# Motor.net
KiCad netlist of a schematic drawn in Altium Designer
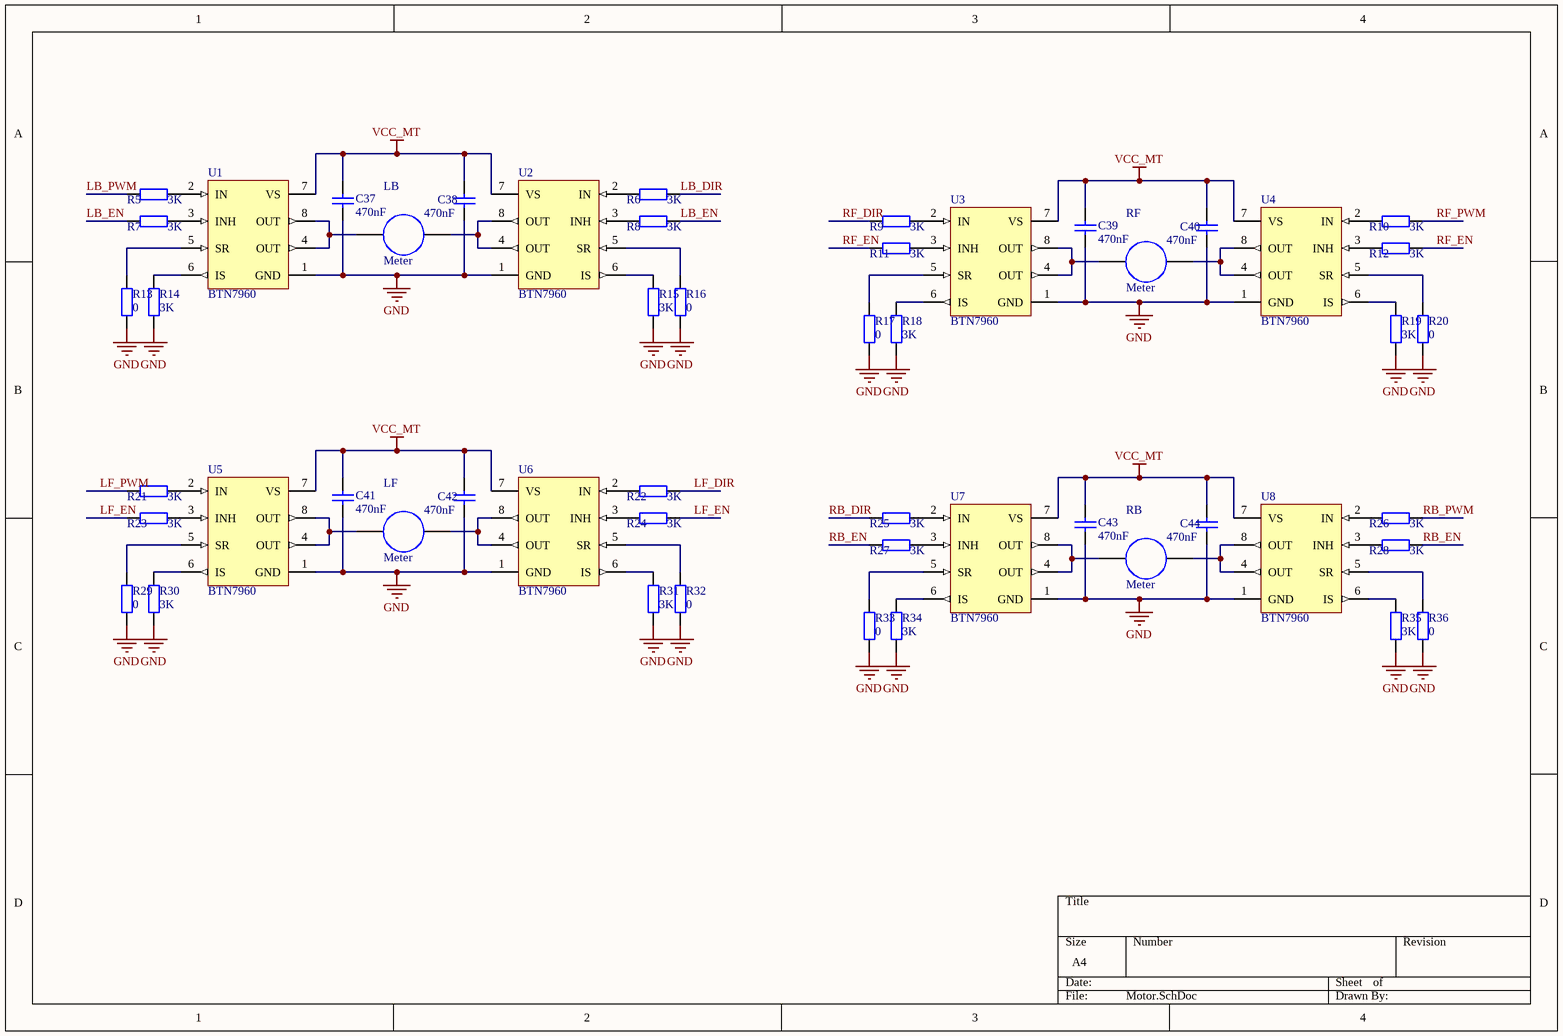
[diagram p0: Motor.SchDoc]

(export (version "E")
  (design (tool "Eeschema 10.0.6"))
  (components
    (comp (ref "C37")
      (value "470nF")
      (footprint "0805_C")
      (description "Capacitor")
      (fields (field (name "Comment") "Cap") (field (name "PUBLISHER") "Altium Limited"))
      (libsource (lib "Miscellaneous Devices") (part "Cap"))
    )
    (comp (ref "C38")
      (value "470nF")
      (footprint "MKV58:0805_C")
      (description "Capacitor")
      (fields (field (name "Comment") "Cap") (field (name "PUBLISHER") "Altium Limited"))
      (libsource (lib "Miscellaneous Devices") (part "Cap"))
    )
    (comp (ref "C39")
      (value "470nF")
      (footprint "0805_C")
      (description "Capacitor")
      (fields (field (name "Comment") "Cap") (field (name "PUBLISHER") "Altium Limited"))
      (libsource (lib "Miscellaneous Devices") (part "Cap"))
    )
    (comp (ref "C40")
      (value "470nF")
      (footprint "MKV58:0805_C")
      (description "Capacitor")
      (fields (field (name "Comment") "Cap") (field (name "PUBLISHER") "Altium Limited"))
      (libsource (lib "Miscellaneous Devices") (part "Cap"))
    )
    (comp (ref "C41")
      (value "470nF")
      (footprint "0805_C")
      (description "Capacitor")
      (fields (field (name "Comment") "Cap") (field (name "PUBLISHER") "Altium Limited"))
      (libsource (lib "Miscellaneous Devices") (part "Cap"))
    )
    (comp (ref "C42")
      (value "470nF")
      (footprint "MKV58:0805_C")
      (description "Capacitor")
      (fields (field (name "Comment") "Cap") (field (name "PUBLISHER") "Altium Limited"))
      (libsource (lib "Miscellaneous Devices") (part "Cap"))
    )
    (comp (ref "C43")
      (value "470nF")
      (footprint "0805_C")
      (description "Capacitor")
      (fields (field (name "Comment") "Cap") (field (name "PUBLISHER") "Altium Limited"))
      (libsource (lib "Miscellaneous Devices") (part "Cap"))
    )
    (comp (ref "C44")
      (value "470nF")
      (footprint "MKV58:0805_C")
      (description "Capacitor")
      (fields (field (name "Comment") "Cap") (field (name "PUBLISHER") "Altium Limited"))
      (libsource (lib "Miscellaneous Devices") (part "Cap"))
    )
    (comp (ref "LB")
      (value "Meter")
      (footprint "Head_Small")
      (description "Indicating Instrument")
      (fields (field (name "PUBLISHER") "Altium Limited"))
      (libsource (lib "Miscellaneous Devices") (part "Meter"))
    )
    (comp (ref "LF")
      (value "Meter")
      (footprint "Head_Small")
      (description "Indicating Instrument")
      (fields (field (name "PUBLISHER") "Altium Limited"))
      (libsource (lib "Miscellaneous Devices") (part "Meter"))
    )
    (comp (ref "R5")
      (value "3K")
      (footprint "0805_R")
      (description "Resistor")
      (fields (field (name "Comment") "Res2") (field (name "PUBLISHER") "Altium Limited"))
      (libsource (lib "") (part "Res2_3"))
    )
    (comp (ref "R6")
      (value "3K")
      (footprint "0805_R")
      (description "Resistor")
      (fields (field (name "Comment") "Res2") (field (name "PUBLISHER") "Altium Limited"))
      (libsource (lib "") (part "Res2_3"))
    )
    (comp (ref "R7")
      (value "3K")
      (footprint "0805_R")
      (description "Resistor")
      (fields (field (name "Comment") "Res2") (field (name "PUBLISHER") "Altium Limited"))
      (libsource (lib "") (part "Res2_2"))
    )
    (comp (ref "R8")
      (value "3K")
      (footprint "0805_R")
      (description "Resistor")
      (fields (field (name "Comment") "Res2") (field (name "PUBLISHER") "Altium Limited"))
      (libsource (lib "Miscellaneous Devices") (part "Res2"))
    )
    (comp (ref "R9")
      (value "3K")
      (footprint "0805_R")
      (description "Resistor")
      (fields (field (name "Comment") "Res2") (field (name "PUBLISHER") "Altium Limited"))
      (libsource (lib "") (part "Res2_3"))
    )
    (comp (ref "R10")
      (value "3K")
      (footprint "0805_R")
      (description "Resistor")
      (fields (field (name "Comment") "Res2") (field (name "PUBLISHER") "Altium Limited"))
      (libsource (lib "") (part "Res2_3"))
    )
    (comp (ref "R11")
      (value "3K")
      (footprint "0805_R")
      (description "Resistor")
      (fields (field (name "Comment") "Res2") (field (name "PUBLISHER") "Altium Limited"))
      (libsource (lib "") (part "Res2_2"))
    )
    (comp (ref "R12")
      (value "3K")
      (footprint "0805_R")
      (description "Resistor")
      (fields (field (name "Comment") "Res2") (field (name "PUBLISHER") "Altium Limited"))
      (libsource (lib "Miscellaneous Devices") (part "Res2"))
    )
    (comp (ref "R13")
      (value "0")
      (footprint "0805_R")
      (description "Resistor")
      (fields (field (name "Comment") "Res2") (field (name "PUBLISHER") "Altium Limited"))
      (libsource (lib "") (part "Res2_1"))
    )
    (comp (ref "R14")
      (value "3K")
      (footprint "0805_R")
      (description "Resistor")
      (fields (field (name "Comment") "Res2") (field (name "PUBLISHER") "Altium Limited"))
      (libsource (lib "") (part "Res2_1"))
    )
    (comp (ref "R15")
      (value "3K")
      (footprint "0805_R")
      (description "Resistor")
      (fields (field (name "Comment") "Res2") (field (name "PUBLISHER") "Altium Limited"))
      (libsource (lib "") (part "Res2_2"))
    )
    (comp (ref "R16")
      (value "0")
      (footprint "0805_R")
      (description "Resistor")
      (fields (field (name "Comment") "Res2") (field (name "PUBLISHER") "Altium Limited"))
      (libsource (lib "") (part "Res2_2"))
    )
    (comp (ref "R17")
      (value "0")
      (footprint "0805_R")
      (description "Resistor")
      (fields (field (name "Comment") "Res2") (field (name "PUBLISHER") "Altium Limited"))
      (libsource (lib "") (part "Res2_1"))
    )
    (comp (ref "R18")
      (value "3K")
      (footprint "0805_R")
      (description "Resistor")
      (fields (field (name "Comment") "Res2") (field (name "PUBLISHER") "Altium Limited"))
      (libsource (lib "") (part "Res2_1"))
    )
    (comp (ref "R19")
      (value "3K")
      (footprint "0805_R")
      (description "Resistor")
      (fields (field (name "Comment") "Res2") (field (name "PUBLISHER") "Altium Limited"))
      (libsource (lib "") (part "Res2_2"))
    )
    (comp (ref "R20")
      (value "0")
      (footprint "0805_R")
      (description "Resistor")
      (fields (field (name "Comment") "Res2") (field (name "PUBLISHER") "Altium Limited"))
      (libsource (lib "") (part "Res2_2"))
    )
    (comp (ref "R21")
      (value "3K")
      (footprint "0805_R")
      (description "Resistor")
      (fields (field (name "Comment") "Res2") (field (name "PUBLISHER") "Altium Limited"))
      (libsource (lib "") (part "Res2_3"))
    )
    (comp (ref "R22")
      (value "3K")
      (footprint "0805_R")
      (description "Resistor")
      (fields (field (name "Comment") "Res2") (field (name "PUBLISHER") "Altium Limited"))
      (libsource (lib "") (part "Res2_3"))
    )
    (comp (ref "R23")
      (value "3K")
      (footprint "0805_R")
      (description "Resistor")
      (fields (field (name "Comment") "Res2") (field (name "PUBLISHER") "Altium Limited"))
      (libsource (lib "") (part "Res2_2"))
    )
    (comp (ref "R24")
      (value "3K")
      (footprint "0805_R")
      (description "Resistor")
      (fields (field (name "Comment") "Res2") (field (name "PUBLISHER") "Altium Limited"))
      (libsource (lib "Miscellaneous Devices") (part "Res2"))
    )
    (comp (ref "R25")
      (value "3K")
      (footprint "0805_R")
      (description "Resistor")
      (fields (field (name "Comment") "Res2") (field (name "PUBLISHER") "Altium Limited"))
      (libsource (lib "") (part "Res2_3"))
    )
    (comp (ref "R26")
      (value "3K")
      (footprint "0805_R")
      (description "Resistor")
      (fields (field (name "Comment") "Res2") (field (name "PUBLISHER") "Altium Limited"))
      (libsource (lib "") (part "Res2_3"))
    )
    (comp (ref "R27")
      (value "3K")
      (footprint "0805_R")
      (description "Resistor")
      (fields (field (name "Comment") "Res2") (field (name "PUBLISHER") "Altium Limited"))
      (libsource (lib "") (part "Res2_2"))
    )
    (comp (ref "R28")
      (value "3K")
      (footprint "0805_R")
      (description "Resistor")
      (fields (field (name "Comment") "Res2") (field (name "PUBLISHER") "Altium Limited"))
      (libsource (lib "Miscellaneous Devices") (part "Res2"))
    )
    (comp (ref "R29")
      (value "0")
      (footprint "0805_R")
      (description "Resistor")
      (fields (field (name "Comment") "Res2") (field (name "PUBLISHER") "Altium Limited"))
      (libsource (lib "") (part "Res2_1"))
    )
    (comp (ref "R30")
      (value "3K")
      (footprint "0805_R")
      (description "Resistor")
      (fields (field (name "Comment") "Res2") (field (name "PUBLISHER") "Altium Limited"))
      (libsource (lib "") (part "Res2_1"))
    )
    (comp (ref "R31")
      (value "3K")
      (footprint "0805_R")
      (description "Resistor")
      (fields (field (name "Comment") "Res2") (field (name "PUBLISHER") "Altium Limited"))
      (libsource (lib "") (part "Res2_2"))
    )
    (comp (ref "R32")
      (value "0")
      (footprint "0805_R")
      (description "Resistor")
      (fields (field (name "Comment") "Res2") (field (name "PUBLISHER") "Altium Limited"))
      (libsource (lib "") (part "Res2_2"))
    )
    (comp (ref "R33")
      (value "0")
      (footprint "0805_R")
      (description "Resistor")
      (fields (field (name "Comment") "Res2") (field (name "PUBLISHER") "Altium Limited"))
      (libsource (lib "") (part "Res2_1"))
    )
    (comp (ref "R34")
      (value "3K")
      (footprint "0805_R")
      (description "Resistor")
      (fields (field (name "Comment") "Res2") (field (name "PUBLISHER") "Altium Limited"))
      (libsource (lib "") (part "Res2_1"))
    )
    (comp (ref "R35")
      (value "3K")
      (footprint "0805_R")
      (description "Resistor")
      (fields (field (name "Comment") "Res2") (field (name "PUBLISHER") "Altium Limited"))
      (libsource (lib "") (part "Res2_2"))
    )
    (comp (ref "R36")
      (value "0")
      (footprint "0805_R")
      (description "Resistor")
      (fields (field (name "Comment") "Res2") (field (name "PUBLISHER") "Altium Limited"))
      (libsource (lib "") (part "Res2_2"))
    )
    (comp (ref "RB")
      (value "Meter")
      (footprint "Head_Small")
      (description "Indicating Instrument")
      (fields (field (name "PUBLISHER") "Altium Limited"))
      (libsource (lib "Miscellaneous Devices") (part "Meter"))
    )
    (comp (ref "RF")
      (value "Meter")
      (footprint "Head_Small")
      (description "Indicating Instrument")
      (fields (field (name "PUBLISHER") "Altium Limited"))
      (libsource (lib "Miscellaneous Devices") (part "Meter"))
    )
    (comp (ref "U1") (value "BTN7960") (footprint "TO-263-7") (libsource (lib "") (part "BTN7960_1")))
    (comp (ref "U2") (value "BTN7960") (footprint "TO-263-7") (libsource (lib "BTN7960") (part "BTN7960")))
    (comp (ref "U3") (value "BTN7960") (footprint "TO-263-7") (libsource (lib "") (part "BTN7960_1")))
    (comp (ref "U4") (value "BTN7960") (footprint "TO-263-7") (libsource (lib "BTN7960") (part "BTN7960")))
    (comp (ref "U5") (value "BTN7960") (footprint "TO-263-7") (libsource (lib "") (part "BTN7960_1")))
    (comp (ref "U6") (value "BTN7960") (footprint "TO-263-7") (libsource (lib "BTN7960") (part "BTN7960")))
    (comp (ref "U7") (value "BTN7960") (footprint "TO-263-7") (libsource (lib "") (part "BTN7960_1")))
    (comp (ref "U8") (value "BTN7960") (footprint "TO-263-7") (libsource (lib "BTN7960") (part "BTN7960")))
  )
  (nets
    (net (code "1") (name "/LB_DIR") (class "Default")
      (node (ref "R6") (pin "1") (pinfunction "1_1") (pintype "passive"))
    )
    (net (code "2") (name "/LB_EN") (class "Default")
      (node (ref "R7") (pin "1") (pinfunction "1_1") (pintype "passive"))
      (node (ref "R8") (pin "1") (pinfunction "1_1") (pintype "passive"))
    )
    (net (code "3") (name "/LB_PWM") (class "Default")
      (node (ref "R5") (pin "2") (pinfunction "2_2") (pintype "passive"))
    )
    (net (code "4") (name "/LF_DIR") (class "Default")
      (node (ref "R22") (pin "1") (pinfunction "1_1") (pintype "passive"))
    )
    (net (code "5") (name "/LF_EN") (class "Default")
      (node (ref "R23") (pin "1") (pinfunction "1_1") (pintype "passive"))
      (node (ref "R24") (pin "1") (pinfunction "1_1") (pintype "passive"))
    )
    (net (code "6") (name "/LF_PWM") (class "Default")
      (node (ref "R21") (pin "2") (pinfunction "2_2") (pintype "passive"))
    )
    (net (code "7") (name "/RB_DIR") (class "Default")
      (node (ref "R25") (pin "2") (pinfunction "2_2") (pintype "passive"))
    )
    (net (code "8") (name "/RB_EN") (class "Default")
      (node (ref "R27") (pin "1") (pinfunction "1_1") (pintype "passive"))
      (node (ref "R28") (pin "1") (pinfunction "1_1") (pintype "passive"))
    )
    (net (code "9") (name "/RB_PWM") (class "Default")
      (node (ref "R26") (pin "1") (pinfunction "1_1") (pintype "passive"))
    )
    (net (code "10") (name "/RF_DIR") (class "Default")
      (node (ref "R9") (pin "2") (pinfunction "2_2") (pintype "passive"))
    )
    (net (code "11") (name "/RF_EN") (class "Default")
      (node (ref "R11") (pin "1") (pinfunction "1_1") (pintype "passive"))
      (node (ref "R12") (pin "1") (pinfunction "1_1") (pintype "passive"))
    )
    (net (code "12") (name "/RF_PWM") (class "Default")
      (node (ref "R10") (pin "1") (pinfunction "1_1") (pintype "passive"))
    )
    (net (code "13") (name "GND") (class "Default")
      (node (ref "C37") (pin "1") (pinfunction "1_1") (pintype "passive"))
      (node (ref "C38") (pin "2") (pinfunction "2_2") (pintype "passive"))
      (node (ref "C39") (pin "1") (pinfunction "1_1") (pintype "passive"))
      (node (ref "C40") (pin "2") (pinfunction "2_2") (pintype "passive"))
      (node (ref "C41") (pin "1") (pinfunction "1_1") (pintype "passive"))
      (node (ref "C42") (pin "2") (pinfunction "2_2") (pintype "passive"))
      (node (ref "C43") (pin "1") (pinfunction "1_1") (pintype "passive"))
      (node (ref "C44") (pin "2") (pinfunction "2_2") (pintype "passive"))
      (node (ref "R13") (pin "1") (pinfunction "1_1") (pintype "passive"))
      (node (ref "R14") (pin "1") (pinfunction "1_1") (pintype "passive"))
      (node (ref "R15") (pin "1") (pinfunction "1_1") (pintype "passive"))
      (node (ref "R16") (pin "1") (pinfunction "1_1") (pintype "passive"))
      (node (ref "R17") (pin "1") (pinfunction "1_1") (pintype "passive"))
      (node (ref "R18") (pin "1") (pinfunction "1_1") (pintype "passive"))
      (node (ref "R19") (pin "1") (pinfunction "1_1") (pintype "passive"))
      (node (ref "R20") (pin "1") (pinfunction "1_1") (pintype "passive"))
      (node (ref "R29") (pin "1") (pinfunction "1_1") (pintype "passive"))
      (node (ref "R30") (pin "1") (pinfunction "1_1") (pintype "passive"))
      (node (ref "R31") (pin "1") (pinfunction "1_1") (pintype "passive"))
      (node (ref "R32") (pin "1") (pinfunction "1_1") (pintype "passive"))
      (node (ref "R33") (pin "1") (pinfunction "1_1") (pintype "passive"))
      (node (ref "R34") (pin "1") (pinfunction "1_1") (pintype "passive"))
      (node (ref "R35") (pin "1") (pinfunction "1_1") (pintype "passive"))
      (node (ref "R36") (pin "1") (pinfunction "1_1") (pintype "passive"))
      (node (ref "U1") (pin "1") (pinfunction "GND_1") (pintype "power_in"))
      (node (ref "U2") (pin "1") (pinfunction "GND_1") (pintype "power_in"))
      (node (ref "U3") (pin "1") (pinfunction "GND_1") (pintype "power_in"))
      (node (ref "U4") (pin "1") (pinfunction "GND_1") (pintype "power_in"))
      (node (ref "U5") (pin "1") (pinfunction "GND_1") (pintype "power_in"))
      (node (ref "U6") (pin "1") (pinfunction "GND_1") (pintype "power_in"))
      (node (ref "U7") (pin "1") (pinfunction "GND_1") (pintype "power_in"))
      (node (ref "U8") (pin "1") (pinfunction "GND_1") (pintype "power_in"))
    )
    (net (code "14") (name "Net-(LB-Pad1)") (class "Default")
      (node (ref "LB") (pin "1") (pinfunction "1_1") (pintype "passive"))
      (node (ref "U1") (pin "4") (pinfunction "OUT_4") (pintype "output"))
      (node (ref "U1") (pin "8") (pinfunction "OUT_8") (pintype "output"))
    )
    (net (code "15") (name "Net-(LB-Pad2)") (class "Default")
      (node (ref "LB") (pin "2") (pinfunction "2_2") (pintype "passive"))
      (node (ref "U2") (pin "4") (pinfunction "OUT_4") (pintype "output"))
      (node (ref "U2") (pin "8") (pinfunction "OUT_8") (pintype "output"))
    )
    (net (code "16") (name "Net-(LF-Pad1)") (class "Default")
      (node (ref "LF") (pin "1") (pinfunction "1_1") (pintype "passive"))
      (node (ref "U5") (pin "4") (pinfunction "OUT_4") (pintype "output"))
      (node (ref "U5") (pin "8") (pinfunction "OUT_8") (pintype "output"))
    )
    (net (code "17") (name "Net-(LF-Pad2)") (class "Default")
      (node (ref "LF") (pin "2") (pinfunction "2_2") (pintype "passive"))
      (node (ref "U6") (pin "4") (pinfunction "OUT_4") (pintype "output"))
      (node (ref "U6") (pin "8") (pinfunction "OUT_8") (pintype "output"))
    )
    (net (code "18") (name "Net-(RB-Pad1)") (class "Default")
      (node (ref "RB") (pin "1") (pinfunction "1_1") (pintype "passive"))
      (node (ref "U7") (pin "4") (pinfunction "OUT_4") (pintype "output"))
      (node (ref "U7") (pin "8") (pinfunction "OUT_8") (pintype "output"))
    )
    (net (code "19") (name "Net-(RB-Pad2)") (class "Default")
      (node (ref "RB") (pin "2") (pinfunction "2_2") (pintype "passive"))
      (node (ref "U8") (pin "4") (pinfunction "OUT_4") (pintype "output"))
      (node (ref "U8") (pin "8") (pinfunction "OUT_8") (pintype "output"))
    )
    (net (code "20") (name "Net-(RF-Pad1)") (class "Default")
      (node (ref "RF") (pin "1") (pinfunction "1_1") (pintype "passive"))
      (node (ref "U3") (pin "4") (pinfunction "OUT_4") (pintype "output"))
      (node (ref "U3") (pin "8") (pinfunction "OUT_8") (pintype "output"))
    )
    (net (code "21") (name "Net-(RF-Pad2)") (class "Default")
      (node (ref "RF") (pin "2") (pinfunction "2_2") (pintype "passive"))
      (node (ref "U4") (pin "4") (pinfunction "OUT_4") (pintype "output"))
      (node (ref "U4") (pin "8") (pinfunction "OUT_8") (pintype "output"))
    )
    (net (code "22") (name "Net-(U1-IN)") (class "Default")
      (node (ref "R5") (pin "1") (pinfunction "1_1") (pintype "passive"))
      (node (ref "U1") (pin "2") (pinfunction "IN_2") (pintype "input"))
    )
    (net (code "23") (name "Net-(U1-INH)") (class "Default")
      (node (ref "R7") (pin "2") (pinfunction "2_2") (pintype "passive"))
      (node (ref "U1") (pin "3") (pinfunction "INH_3") (pintype "input"))
    )
    (net (code "24") (name "Net-(U1-IS)") (class "Default")
      (node (ref "R14") (pin "2") (pinfunction "2_2") (pintype "passive"))
      (node (ref "U1") (pin "6") (pinfunction "IS_6") (pintype "output"))
    )
    (net (code "25") (name "Net-(U1-SR)") (class "Default")
      (node (ref "R13") (pin "2") (pinfunction "2_2") (pintype "passive"))
      (node (ref "U1") (pin "5") (pinfunction "SR_5") (pintype "input"))
    )
    (net (code "26") (name "Net-(U2-IN)") (class "Default")
      (node (ref "R6") (pin "2") (pinfunction "2_2") (pintype "passive"))
      (node (ref "U2") (pin "2") (pinfunction "IN_2") (pintype "input"))
    )
    (net (code "27") (name "Net-(U2-INH)") (class "Default")
      (node (ref "R8") (pin "2") (pinfunction "2_2") (pintype "passive"))
      (node (ref "U2") (pin "3") (pinfunction "INH_3") (pintype "input"))
    )
    (net (code "28") (name "Net-(U2-IS)") (class "Default")
      (node (ref "R15") (pin "2") (pinfunction "2_2") (pintype "passive"))
      (node (ref "U2") (pin "6") (pinfunction "IS_6") (pintype "output"))
    )
    (net (code "29") (name "Net-(U2-SR)") (class "Default")
      (node (ref "R16") (pin "2") (pinfunction "2_2") (pintype "passive"))
      (node (ref "U2") (pin "5") (pinfunction "SR_5") (pintype "input"))
    )
    (net (code "30") (name "Net-(U3-IN)") (class "Default")
      (node (ref "R9") (pin "1") (pinfunction "1_1") (pintype "passive"))
      (node (ref "U3") (pin "2") (pinfunction "IN_2") (pintype "input"))
    )
    (net (code "31") (name "Net-(U3-INH)") (class "Default")
      (node (ref "R11") (pin "2") (pinfunction "2_2") (pintype "passive"))
      (node (ref "U3") (pin "3") (pinfunction "INH_3") (pintype "input"))
    )
    (net (code "32") (name "Net-(U3-IS)") (class "Default")
      (node (ref "R18") (pin "2") (pinfunction "2_2") (pintype "passive"))
      (node (ref "U3") (pin "6") (pinfunction "IS_6") (pintype "output"))
    )
    (net (code "33") (name "Net-(U3-SR)") (class "Default")
      (node (ref "R17") (pin "2") (pinfunction "2_2") (pintype "passive"))
      (node (ref "U3") (pin "5") (pinfunction "SR_5") (pintype "input"))
    )
    (net (code "34") (name "Net-(U4-IN)") (class "Default")
      (node (ref "R10") (pin "2") (pinfunction "2_2") (pintype "passive"))
      (node (ref "U4") (pin "2") (pinfunction "IN_2") (pintype "input"))
    )
    (net (code "35") (name "Net-(U4-INH)") (class "Default")
      (node (ref "R12") (pin "2") (pinfunction "2_2") (pintype "passive"))
      (node (ref "U4") (pin "3") (pinfunction "INH_3") (pintype "input"))
    )
    (net (code "36") (name "Net-(U4-IS)") (class "Default")
      (node (ref "R19") (pin "2") (pinfunction "2_2") (pintype "passive"))
      (node (ref "U4") (pin "6") (pinfunction "IS_6") (pintype "output"))
    )
    (net (code "37") (name "Net-(U4-SR)") (class "Default")
      (node (ref "R20") (pin "2") (pinfunction "2_2") (pintype "passive"))
      (node (ref "U4") (pin "5") (pinfunction "SR_5") (pintype "input"))
    )
    (net (code "38") (name "Net-(U5-IN)") (class "Default")
      (node (ref "R21") (pin "1") (pinfunction "1_1") (pintype "passive"))
      (node (ref "U5") (pin "2") (pinfunction "IN_2") (pintype "input"))
    )
    (net (code "39") (name "Net-(U5-INH)") (class "Default")
      (node (ref "R23") (pin "2") (pinfunction "2_2") (pintype "passive"))
      (node (ref "U5") (pin "3") (pinfunction "INH_3") (pintype "input"))
    )
    (net (code "40") (name "Net-(U5-IS)") (class "Default")
      (node (ref "R30") (pin "2") (pinfunction "2_2") (pintype "passive"))
      (node (ref "U5") (pin "6") (pinfunction "IS_6") (pintype "output"))
    )
    (net (code "41") (name "Net-(U5-SR)") (class "Default")
      (node (ref "R29") (pin "2") (pinfunction "2_2") (pintype "passive"))
      (node (ref "U5") (pin "5") (pinfunction "SR_5") (pintype "input"))
    )
    (net (code "42") (name "Net-(U6-IN)") (class "Default")
      (node (ref "R22") (pin "2") (pinfunction "2_2") (pintype "passive"))
      (node (ref "U6") (pin "2") (pinfunction "IN_2") (pintype "input"))
    )
    (net (code "43") (name "Net-(U6-INH)") (class "Default")
      (node (ref "R24") (pin "2") (pinfunction "2_2") (pintype "passive"))
      (node (ref "U6") (pin "3") (pinfunction "INH_3") (pintype "input"))
    )
    (net (code "44") (name "Net-(U6-IS)") (class "Default")
      (node (ref "R31") (pin "2") (pinfunction "2_2") (pintype "passive"))
      (node (ref "U6") (pin "6") (pinfunction "IS_6") (pintype "output"))
    )
    (net (code "45") (name "Net-(U6-SR)") (class "Default")
      (node (ref "R32") (pin "2") (pinfunction "2_2") (pintype "passive"))
      (node (ref "U6") (pin "5") (pinfunction "SR_5") (pintype "input"))
    )
    (net (code "46") (name "Net-(U7-IN)") (class "Default")
      (node (ref "R25") (pin "1") (pinfunction "1_1") (pintype "passive"))
      (node (ref "U7") (pin "2") (pinfunction "IN_2") (pintype "input"))
    )
    (net (code "47") (name "Net-(U7-INH)") (class "Default")
      (node (ref "R27") (pin "2") (pinfunction "2_2") (pintype "passive"))
      (node (ref "U7") (pin "3") (pinfunction "INH_3") (pintype "input"))
    )
    (net (code "48") (name "Net-(U7-IS)") (class "Default")
      (node (ref "R34") (pin "2") (pinfunction "2_2") (pintype "passive"))
      (node (ref "U7") (pin "6") (pinfunction "IS_6") (pintype "output"))
    )
    (net (code "49") (name "Net-(U7-SR)") (class "Default")
      (node (ref "R33") (pin "2") (pinfunction "2_2") (pintype "passive"))
      (node (ref "U7") (pin "5") (pinfunction "SR_5") (pintype "input"))
    )
    (net (code "50") (name "Net-(U8-IN)") (class "Default")
      (node (ref "R26") (pin "2") (pinfunction "2_2") (pintype "passive"))
      (node (ref "U8") (pin "2") (pinfunction "IN_2") (pintype "input"))
    )
    (net (code "51") (name "Net-(U8-INH)") (class "Default")
      (node (ref "R28") (pin "2") (pinfunction "2_2") (pintype "passive"))
      (node (ref "U8") (pin "3") (pinfunction "INH_3") (pintype "input"))
    )
    (net (code "52") (name "Net-(U8-IS)") (class "Default")
      (node (ref "R35") (pin "2") (pinfunction "2_2") (pintype "passive"))
      (node (ref "U8") (pin "6") (pinfunction "IS_6") (pintype "output"))
    )
    (net (code "53") (name "Net-(U8-SR)") (class "Default")
      (node (ref "R36") (pin "2") (pinfunction "2_2") (pintype "passive"))
      (node (ref "U8") (pin "5") (pinfunction "SR_5") (pintype "input"))
    )
    (net (code "54") (name "VCC_MT") (class "Default")
      (node (ref "C37") (pin "2") (pinfunction "2_2") (pintype "passive"))
      (node (ref "C38") (pin "1") (pinfunction "1_1") (pintype "passive"))
      (node (ref "C39") (pin "2") (pinfunction "2_2") (pintype "passive"))
      (node (ref "C40") (pin "1") (pinfunction "1_1") (pintype "passive"))
      (node (ref "C41") (pin "2") (pinfunction "2_2") (pintype "passive"))
      (node (ref "C42") (pin "1") (pinfunction "1_1") (pintype "passive"))
      (node (ref "C43") (pin "2") (pinfunction "2_2") (pintype "passive"))
      (node (ref "C44") (pin "1") (pinfunction "1_1") (pintype "passive"))
      (node (ref "U1") (pin "7") (pinfunction "VS_7") (pintype "power_in"))
      (node (ref "U2") (pin "7") (pinfunction "VS_7") (pintype "power_in"))
      (node (ref "U3") (pin "7") (pinfunction "VS_7") (pintype "power_in"))
      (node (ref "U4") (pin "7") (pinfunction "VS_7") (pintype "power_in"))
      (node (ref "U5") (pin "7") (pinfunction "VS_7") (pintype "power_in"))
      (node (ref "U6") (pin "7") (pinfunction "VS_7") (pintype "power_in"))
      (node (ref "U7") (pin "7") (pinfunction "VS_7") (pintype "power_in"))
      (node (ref "U8") (pin "7") (pinfunction "VS_7") (pintype "power_in"))
    )
  )
)
